# MEMS-preamp_v03.net
KiCad netlist of a schematic drawn in EAGLE
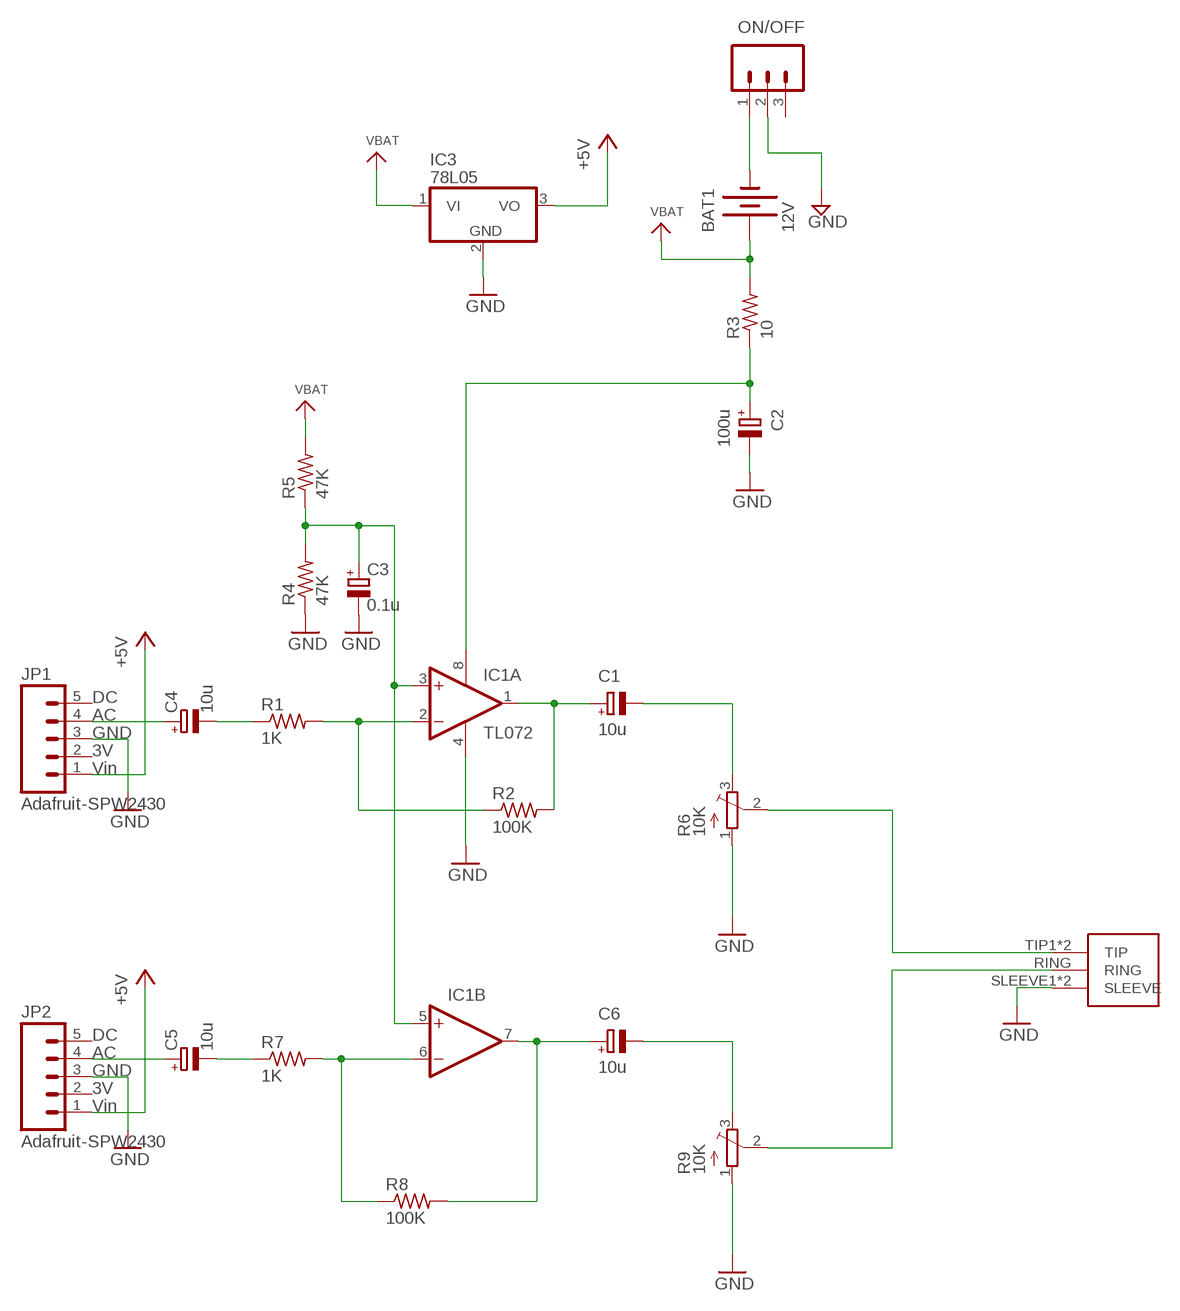
[diagram p0: schematic, sheet 1]

(export (version "E")
  (design (tool "Eeschema 10.0.6"))
  (components
    (comp (ref "BAT1")
      (value "12V")
      (footprint "eagle-import:BATTERY-A23")
      (libsource (lib "eagle-import") (part "BATTERYA23"))
    )
    (comp (ref "C1")
      (value "10u")
      (footprint "eagle-import:E2,5-5")
      (libsource (lib "eagle-import") (part "CPOL-EUE2.5-5"))
    )
    (comp (ref "C2")
      (value "100u")
      (footprint "eagle-import:E2,5-5")
      (libsource (lib "eagle-import") (part "CPOL-EUE2.5-5"))
    )
    (comp (ref "C3")
      (value "0.1u")
      (footprint "eagle-import:E2,5-5")
      (libsource (lib "eagle-import") (part "CPOL-EUE2.5-5"))
    )
    (comp (ref "C4")
      (value "10u")
      (footprint "eagle-import:E2,5-5")
      (libsource (lib "eagle-import") (part "CPOL-EUE2.5-5"))
    )
    (comp (ref "C5")
      (value "10u")
      (footprint "eagle-import:E2,5-5")
      (libsource (lib "eagle-import") (part "CPOL-EUE2.5-5"))
    )
    (comp (ref "C6")
      (value "10u")
      (footprint "eagle-import:E2,5-5")
      (libsource (lib "eagle-import") (part "CPOL-EUE2.5-5"))
    )
    (comp (ref "IC1")
      (value "OPA2134PA")
      (footprint "eagle-import:DIL08")
      (fields (field (name "IC_NAME") "TL072"))
      (libsource (lib "eagle-import") (part "OPA2PA134"))
    )
    (comp (ref "IC3")
      (value "78L05")
      (footprint "eagle-import:TO92-")
      (libsource (lib "eagle-import") (part "78"))
    )
    (comp (ref "JP1")
      (value "Adafruit-SPW2430")
      (footprint "eagle-import:1X05_LOCK")
      (fields
        (field (name "CON1") "Vin")
        (field (name "CON2") "3V")
        (field (name "CON3") "GND")
        (field (name "CON4") "AC")
        (field (name "CON5") "DC")
      )
      (libsource (lib "eagle-import") (part "M05LOCK"))
    )
    (comp (ref "JP2")
      (value "Adafruit-SPW2430")
      (footprint "eagle-import:1X05_LOCK")
      (fields
        (field (name "CON1") "Vin")
        (field (name "CON2") "3V")
        (field (name "CON3") "GND")
        (field (name "CON4") "AC")
        (field (name "CON5") "DC")
      )
      (libsource (lib "eagle-import") (part "M05LOCK"))
    )
    (comp (ref "ON/OFF")
      (value "labl")
      (footprint "eagle-import:SPDT-SWITCH")
      (libsource (lib "eagle-import") (part "M03SINGLE-POLE-DOUBLE-THROW"))
    )
    (comp (ref "R1")
      (value "1K")
      (footprint "eagle-import:0204V")
      (libsource (lib "eagle-import") (part "R-US_0204/2V"))
    )
    (comp (ref "R2")
      (value "100K")
      (footprint "eagle-import:0204V")
      (libsource (lib "eagle-import") (part "R-US_0204/2V"))
    )
    (comp (ref "R3")
      (value "10")
      (footprint "eagle-import:0204V")
      (libsource (lib "eagle-import") (part "R-US_0204/2V"))
    )
    (comp (ref "R4")
      (value "47K")
      (footprint "eagle-import:0204V")
      (libsource (lib "eagle-import") (part "R-US_0204/2V"))
    )
    (comp (ref "R5")
      (value "47K")
      (footprint "eagle-import:0204V")
      (libsource (lib "eagle-import") (part "R-US_0204/2V"))
    )
    (comp (ref "R6")
      (value "10K")
      (footprint "eagle-import:TRIM-3386")
      (libsource (lib "eagle-import") (part "TRIMPOT3386"))
    )
    (comp (ref "R7")
      (value "1K")
      (footprint "eagle-import:0204V")
      (libsource (lib "eagle-import") (part "R-US_0204/2V"))
    )
    (comp (ref "R8")
      (value "100K")
      (footprint "eagle-import:0204V")
      (libsource (lib "eagle-import") (part "R-US_0204/2V"))
    )
    (comp (ref "R9")
      (value "10K")
      (footprint "eagle-import:TRIM-3386")
      (libsource (lib "eagle-import") (part "TRIMPOT3386"))
    )
    (comp (ref "U$1")
      (value "1/8\"-F-STEREO-PCB")
      (footprint "eagle-import:1_8_-F-STEREO-PCB")
      (libsource (lib "eagle-import") (part "1/8{dblquote}-F-STEREO-PCB"))
    )
  )
  (nets
    (net (code "1") (name "+5V") (class "Default")
      (node (ref "IC3") (pin "3") (pinfunction "VO_3") (pintype "passive"))
      (node (ref "JP1") (pin "1") (pinfunction "1_1") (pintype "passive"))
      (node (ref "JP2") (pin "1") (pinfunction "1_1") (pintype "passive"))
    )
    (net (code "2") (name "GND") (class "Default")
      (node (ref "C2") (pin "-") (pinfunction "-_-") (pintype "passive"))
      (node (ref "C3") (pin "-") (pinfunction "-_-") (pintype "passive"))
      (node (ref "IC1") (pin "4") (pinfunction "V-_4") (pintype "power_in"))
      (node (ref "IC3") (pin "2") (pinfunction "GND_2") (pintype "passive"))
      (node (ref "JP1") (pin "3") (pinfunction "3_3") (pintype "passive"))
      (node (ref "JP2") (pin "3") (pinfunction "3_3") (pintype "passive"))
      (node (ref "ON/OFF") (pin "2") (pinfunction "2_2") (pintype "passive"))
      (node (ref "R4") (pin "1") (pinfunction "1_1") (pintype "passive"))
      (node (ref "R6") (pin "1") (pinfunction "A_1") (pintype "passive"))
      (node (ref "R9") (pin "1") (pinfunction "A_1") (pintype "passive"))
      (node (ref "U$1") (pin "SLEEVE1") (pinfunction "SLEEVE_SLEEVE1") (pintype "bidirectional"))
      (node (ref "U$1") (pin "SLEEVE2") (pinfunction "SLEEVE_SLEEVE2") (pintype "bidirectional"))
    )
    (net (code "3") (name "Net-(BAT1--)") (class "Default")
      (node (ref "BAT1") (pin "GND@1") (pinfunction "-_GND@1") (pintype "power_in"))
      (node (ref "ON/OFF") (pin "1") (pinfunction "1_1") (pintype "passive"))
    )
    (net (code "4") (name "Net-(C4-Pad+)") (class "Default")
      (node (ref "C4") (pin "+") (pinfunction "+_+") (pintype "passive"))
      (node (ref "JP1") (pin "4") (pinfunction "4_4") (pintype "passive"))
    )
    (net (code "5") (name "Net-(C4-Pad-)") (class "Default")
      (node (ref "C4") (pin "-") (pinfunction "-_-") (pintype "passive"))
      (node (ref "R1") (pin "1") (pinfunction "1_1") (pintype "passive"))
    )
    (net (code "6") (name "Net-(C5-Pad+)") (class "Default")
      (node (ref "C5") (pin "+") (pinfunction "+_+") (pintype "passive"))
      (node (ref "JP2") (pin "4") (pinfunction "4_4") (pintype "passive"))
    )
    (net (code "7") (name "Net-(C5-Pad-)") (class "Default")
      (node (ref "C5") (pin "-") (pinfunction "-_-") (pintype "passive"))
      (node (ref "R7") (pin "1") (pinfunction "1_1") (pintype "passive"))
    )
    (net (code "8") (name "Net-(IC1A-+IN)") (class "Default")
      (node (ref "C3") (pin "+") (pinfunction "+_+") (pintype "passive"))
      (node (ref "IC1") (pin "3") (pinfunction "+IN_3") (pintype "input"))
      (node (ref "IC1") (pin "5") (pinfunction "+IN_5") (pintype "input"))
      (node (ref "R4") (pin "2") (pinfunction "2_2") (pintype "passive"))
      (node (ref "R5") (pin "1") (pinfunction "1_1") (pintype "passive"))
    )
    (net (code "9") (name "Net-(IC1A--IN)") (class "Default")
      (node (ref "IC1") (pin "2") (pinfunction "-IN_2") (pintype "input"))
      (node (ref "R1") (pin "2") (pinfunction "2_2") (pintype "passive"))
      (node (ref "R2") (pin "1") (pinfunction "1_1") (pintype "passive"))
    )
    (net (code "10") (name "Net-(IC1A-OUT)") (class "Default")
      (node (ref "C1") (pin "+") (pinfunction "+_+") (pintype "passive"))
      (node (ref "IC1") (pin "1") (pinfunction "OUT_1") (pintype "output"))
      (node (ref "R2") (pin "2") (pinfunction "2_2") (pintype "passive"))
    )
    (net (code "11") (name "Net-(IC1A-V+)") (class "Default")
      (node (ref "C2") (pin "+") (pinfunction "+_+") (pintype "passive"))
      (node (ref "IC1") (pin "8") (pinfunction "V+_8") (pintype "power_in"))
      (node (ref "R3") (pin "1") (pinfunction "1_1") (pintype "passive"))
    )
    (net (code "12") (name "Net-(IC1B--IN)") (class "Default")
      (node (ref "IC1") (pin "6") (pinfunction "-IN_6") (pintype "input"))
      (node (ref "R7") (pin "2") (pinfunction "2_2") (pintype "passive"))
      (node (ref "R8") (pin "1") (pinfunction "1_1") (pintype "passive"))
    )
    (net (code "13") (name "Net-(IC1B-OUT)") (class "Default")
      (node (ref "C6") (pin "+") (pinfunction "+_+") (pintype "passive"))
      (node (ref "IC1") (pin "7") (pinfunction "OUT_7") (pintype "output"))
      (node (ref "R8") (pin "2") (pinfunction "2_2") (pintype "passive"))
    )
    (net (code "14") (name "Net-(R6-E)") (class "Default")
      (node (ref "C1") (pin "-") (pinfunction "-_-") (pintype "passive"))
      (node (ref "R6") (pin "3") (pinfunction "E_3") (pintype "passive"))
    )
    (net (code "15") (name "Net-(R6-S)") (class "Default")
      (node (ref "R6") (pin "2") (pinfunction "S_2") (pintype "passive"))
      (node (ref "U$1") (pin "TIP1") (pinfunction "TIP_TIP1") (pintype "bidirectional"))
      (node (ref "U$1") (pin "TIP2") (pinfunction "TIP_TIP2") (pintype "bidirectional"))
    )
    (net (code "16") (name "Net-(R9-E)") (class "Default")
      (node (ref "C6") (pin "-") (pinfunction "-_-") (pintype "passive"))
      (node (ref "R9") (pin "3") (pinfunction "E_3") (pintype "passive"))
    )
    (net (code "17") (name "Net-(R9-S)") (class "Default")
      (node (ref "R9") (pin "2") (pinfunction "S_2") (pintype "passive"))
      (node (ref "U$1") (pin "RING") (pinfunction "RING_RING") (pintype "bidirectional"))
    )
    (net (code "18") (name "VBAT") (class "Default")
      (node (ref "BAT1") (pin "PWR@1") (pinfunction "+_PWR@1") (pintype "power_in"))
      (node (ref "IC3") (pin "1") (pinfunction "VI_1") (pintype "input"))
      (node (ref "R3") (pin "2") (pinfunction "2_2") (pintype "passive"))
      (node (ref "R5") (pin "2") (pinfunction "2_2") (pintype "passive"))
    )
    (net (code "19") (name "unconnected-(JP1-Pad2)") (class "Default")
      (node (ref "JP1") (pin "2") (pinfunction "2_2") (pintype "passive"))
    )
    (net (code "20") (name "unconnected-(JP1-Pad5)") (class "Default")
      (node (ref "JP1") (pin "5") (pinfunction "5_5") (pintype "passive"))
    )
    (net (code "21") (name "unconnected-(JP2-Pad2)") (class "Default")
      (node (ref "JP2") (pin "2") (pinfunction "2_2") (pintype "passive"))
    )
    (net (code "22") (name "unconnected-(JP2-Pad5)") (class "Default")
      (node (ref "JP2") (pin "5") (pinfunction "5_5") (pintype "passive"))
    )
    (net (code "23") (name "unconnected-(ON/OFF-Pad3)") (class "Default")
      (node (ref "ON/OFF") (pin "3") (pinfunction "3_3") (pintype "passive"))
    )
  )
)
